# Anchor.net
KiCad netlist of a schematic drawn in Altium Designer
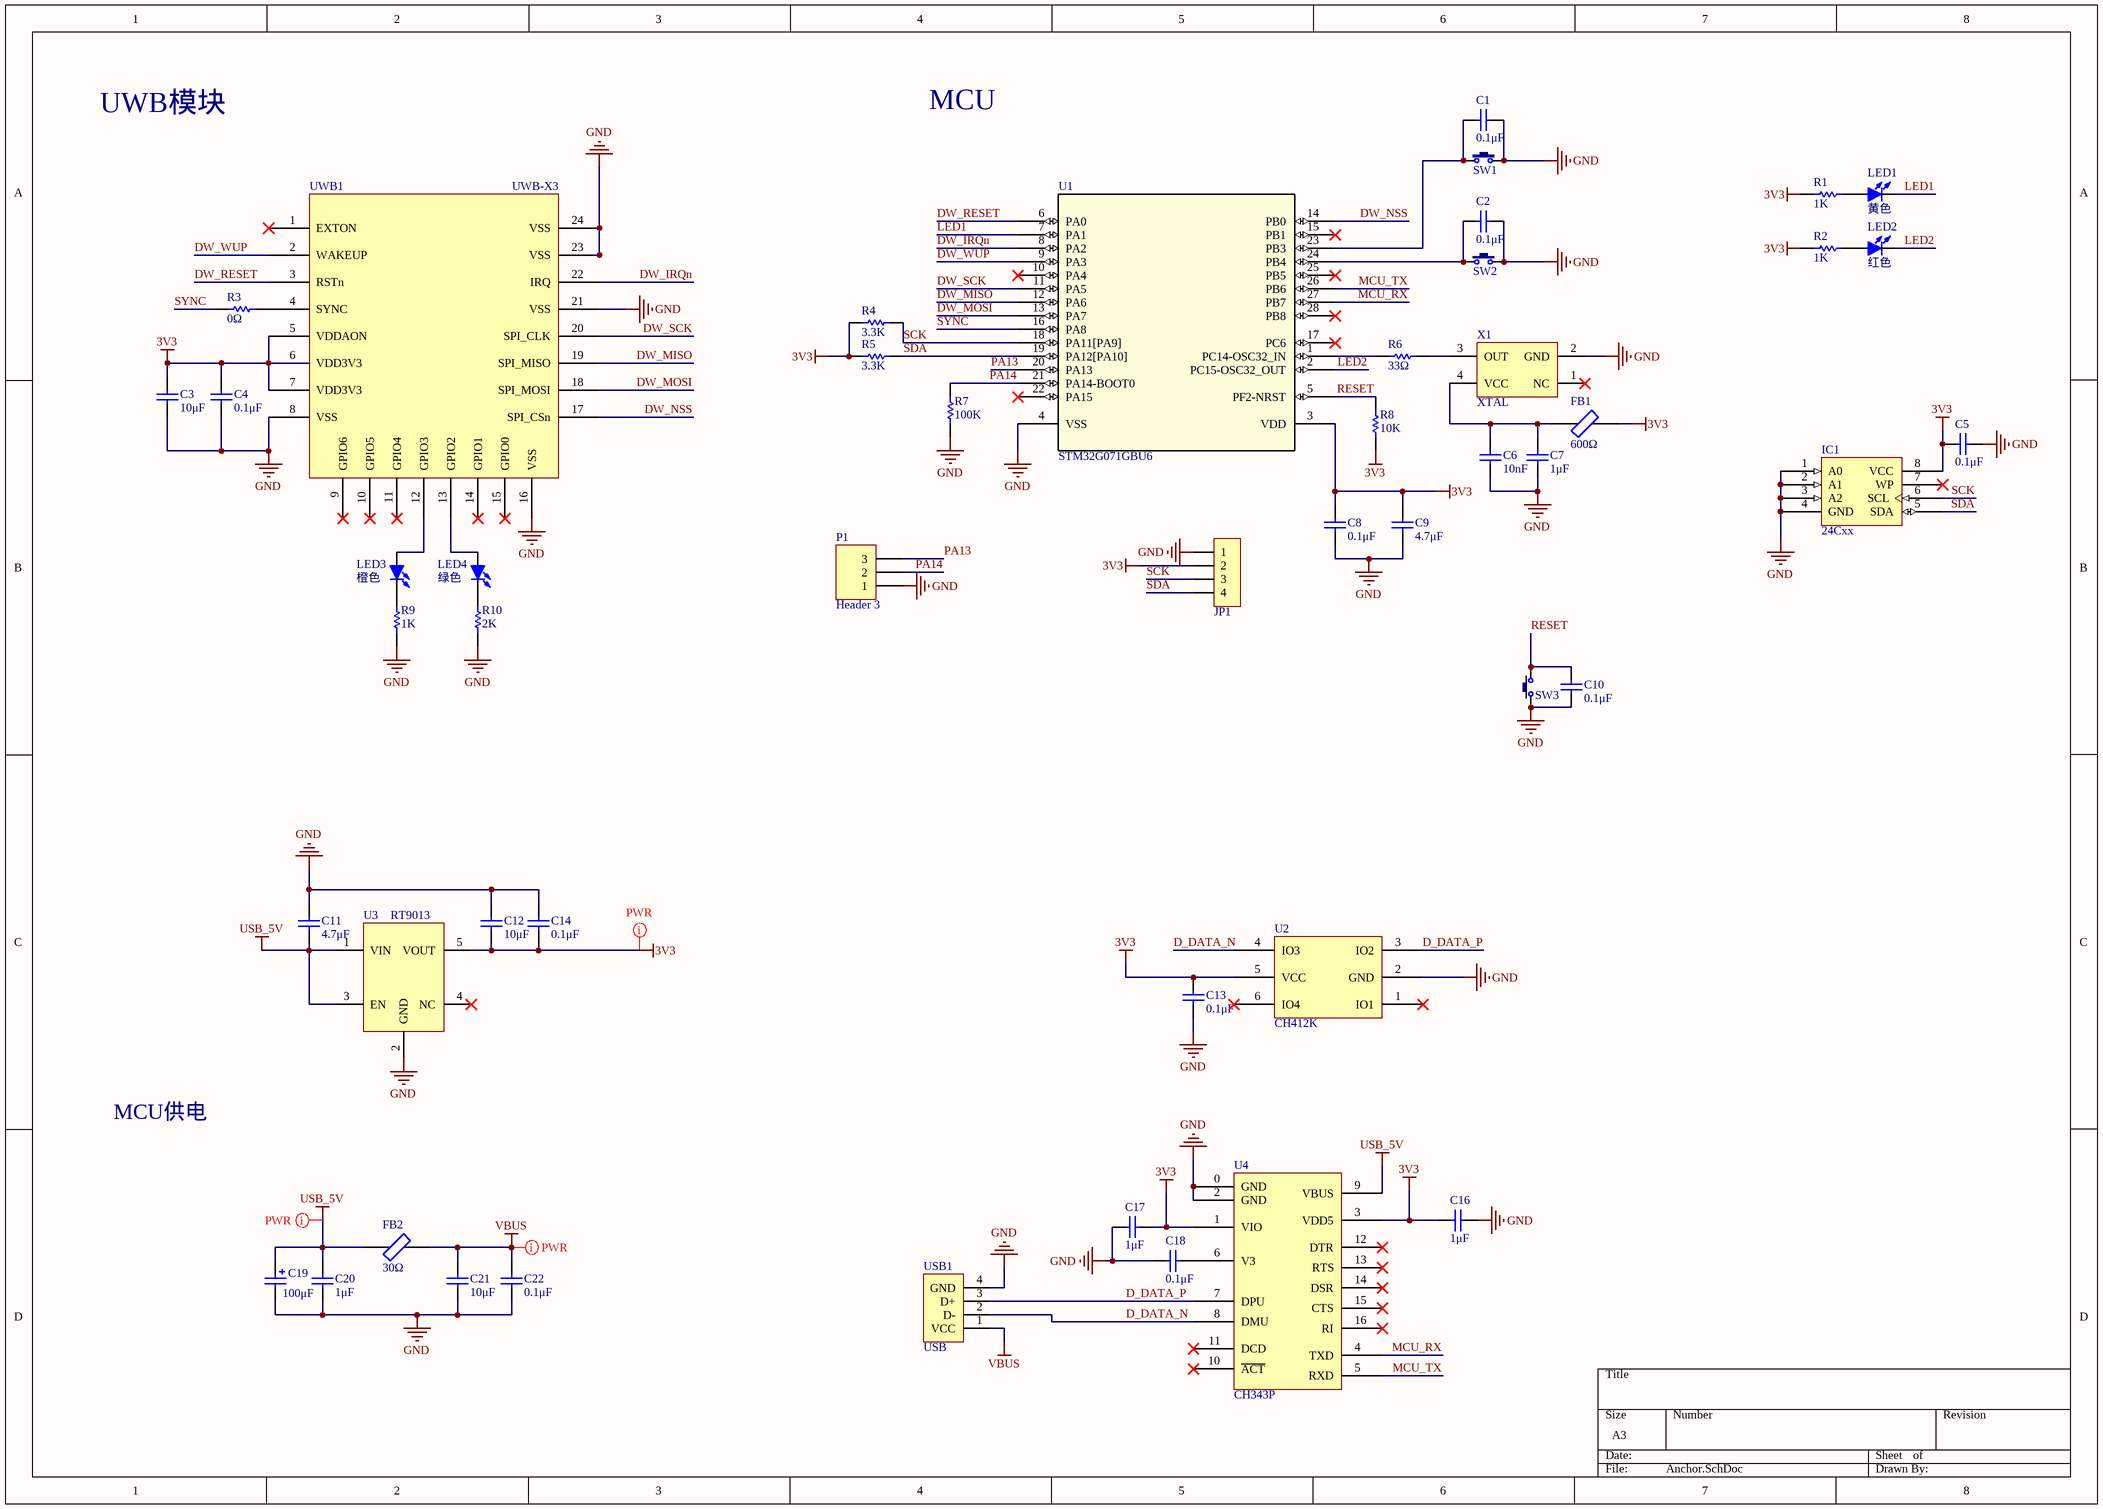
[diagram p0: Anchor.SchDoc]

(export (version "E")
  (design (tool "Eeschema 10.0.6"))
  (components
    (comp (ref "C1")
      (value "0.1μF")
      (footprint "C 0603_L")
      (description "Capacitor")
      (fields (field (name "Comment") "Cap") (field (name "PUBLISHER") "Altium Limited"))
      (libsource (lib "Nixie") (part "Cap"))
    )
    (comp (ref "C2")
      (value "0.1μF")
      (footprint "C 0603_L")
      (description "Capacitor")
      (fields (field (name "Comment") "Cap") (field (name "PUBLISHER") "Altium Limited"))
      (libsource (lib "Nixie") (part "Cap"))
    )
    (comp (ref "C3")
      (value "10μF")
      (footprint "C 0603_L")
      (description "Capacitor")
      (fields (field (name "Comment") "Cap") (field (name "PUBLISHER") "Altium Limited"))
      (libsource (lib "Nixie") (part "Cap"))
    )
    (comp (ref "C4")
      (value "0.1μF")
      (footprint "C 0603_L")
      (description "Capacitor")
      (fields (field (name "Comment") "Cap") (field (name "PUBLISHER") "Altium Limited"))
      (libsource (lib "Nixie") (part "Cap"))
    )
    (comp (ref "C5")
      (value "0.1μF")
      (footprint "C 0603_L")
      (description "Capacitor")
      (fields (field (name "Comment") "Cap") (field (name "PUBLISHER") "Altium Limited"))
      (libsource (lib "Nixie") (part "Cap"))
    )
    (comp (ref "C6")
      (value "10nF")
      (footprint "C 0603_L")
      (description "Capacitor")
      (fields (field (name "Comment") "Cap") (field (name "PUBLISHER") "Altium Limited"))
      (libsource (lib "Nixie") (part "Cap"))
    )
    (comp (ref "C7")
      (value "1μF")
      (footprint "C 0603_L")
      (description "Capacitor")
      (fields (field (name "Comment") "Cap") (field (name "PUBLISHER") "Altium Limited"))
      (libsource (lib "Nixie") (part "Cap"))
    )
    (comp (ref "C8")
      (value "0.1μF")
      (footprint "C 0603_L")
      (description "Capacitor")
      (fields (field (name "Comment") "Cap") (field (name "PUBLISHER") "Altium Limited"))
      (libsource (lib "Nixie") (part "Cap"))
    )
    (comp (ref "C9")
      (value "4.7μF")
      (footprint "C 0603_L")
      (description "Capacitor")
      (fields (field (name "Comment") "Cap") (field (name "PUBLISHER") "Altium Limited"))
      (libsource (lib "Nixie") (part "Cap"))
    )
    (comp (ref "C10")
      (value "0.1μF")
      (footprint "C 0603_L")
      (description "Capacitor")
      (fields (field (name "Comment") "Cap") (field (name "PUBLISHER") "Altium Limited"))
      (libsource (lib "Nixie") (part "Cap"))
    )
    (comp (ref "C11")
      (value "4.7μF")
      (footprint "C 0603_L")
      (description "Capacitor")
      (fields (field (name "Comment") "Cap") (field (name "PUBLISHER") "Altium Limited"))
      (libsource (lib "Nixie") (part "Cap"))
    )
    (comp (ref "C12")
      (value "10μF")
      (footprint "C 0603_L")
      (description "Capacitor")
      (fields (field (name "Comment") "Cap") (field (name "PUBLISHER") "Altium Limited"))
      (libsource (lib "Nixie") (part "Cap"))
    )
    (comp (ref "C13")
      (value "0.1μF")
      (footprint "C 0603_L")
      (description "Capacitor")
      (fields (field (name "Comment") "Cap") (field (name "PUBLISHER") "Altium Limited"))
      (libsource (lib "Nixie") (part "Cap"))
    )
    (comp (ref "C14")
      (value "0.1μF")
      (footprint "C 0603_L")
      (description "Capacitor")
      (fields (field (name "Comment") "Cap") (field (name "PUBLISHER") "Altium Limited"))
      (libsource (lib "Nixie") (part "Cap"))
    )
    (comp (ref "C16")
      (value "1μF")
      (footprint "C 0603_L")
      (description "Capacitor")
      (fields (field (name "Comment") "Cap") (field (name "PUBLISHER") "Altium Limited"))
      (libsource (lib "Nixie") (part "Cap"))
    )
    (comp (ref "C17")
      (value "1μF")
      (footprint "C 0603_L")
      (description "Capacitor")
      (fields (field (name "Comment") "Cap") (field (name "PUBLISHER") "Altium Limited"))
      (libsource (lib "Nixie") (part "Cap"))
    )
    (comp (ref "C18")
      (value "0.1μF")
      (footprint "C 0603_L")
      (description "Capacitor")
      (fields (field (name "Comment") "Cap") (field (name "PUBLISHER") "Altium Limited"))
      (libsource (lib "Nixie") (part "Cap"))
    )
    (comp (ref "C19")
      (value "100μF")
      (footprint "CM C(5*5.4)")
      (description "Polarized Capacitor (Radial)")
      (fields (field (name "Comment") "Cap Pol1") (field (name "PUBLISHER") "Altium Limited"))
      (libsource (lib "Nixie") (part "Cap Pol1"))
    )
    (comp (ref "C20")
      (value "1μF")
      (footprint "C 0603_L")
      (description "Capacitor")
      (fields (field (name "Comment") "Cap") (field (name "PUBLISHER") "Altium Limited"))
      (libsource (lib "Nixie") (part "Cap"))
    )
    (comp (ref "C21")
      (value "10μF")
      (footprint "C 0603_L")
      (description "Capacitor")
      (fields (field (name "Comment") "Cap") (field (name "PUBLISHER") "Altium Limited"))
      (libsource (lib "Nixie") (part "Cap"))
    )
    (comp (ref "C22")
      (value "0.1μF")
      (footprint "C 0603_L")
      (description "Capacitor")
      (fields (field (name "Comment") "Cap") (field (name "PUBLISHER") "Altium Limited"))
      (libsource (lib "Nixie") (part "Cap"))
    )
    (comp (ref "FB1")
      (value "600Ω")
      (footprint "C 0603_L")
      (description "铁氧体磁珠")
      (fields (field (name "Comment") "Ferrite bead"))
      (libsource (lib "Nixie") (part "Ferrite bead"))
    )
    (comp (ref "FB2")
      (value "30Ω")
      (footprint "C 0603_L")
      (description "铁氧体磁珠")
      (fields (field (name "Comment") "Ferrite bead"))
      (libsource (lib "Nixie") (part "Ferrite bead"))
    )
    (comp (ref "IC1")
      (value "24Cxx")
      (footprint "SOP8_L")
      (description "外置EEPROM")
      (fields (field (name "版权归属") "封装库来自淘宝 ID：黄晶宝石"))
      (libsource (lib "Nixie") (part "24Cxx"))
    )
    (comp (ref "JP1")
      (value "HDR-1X4")
      (footprint "HDR2.54-LI-4P")
      (description "4P接插件")
      (fields (field (name "版权归属") "封装库来自淘宝 ID：黄晶宝石"))
      (libsource (lib "Nixie") (part "Header 4"))
    )
    (comp (ref "LED1")
      (value "黄色")
      (footprint "LED 0805G")
      (description "贴片LED")
      (fields (field (name "版权归属") "封装库来自淘宝 ID：黄晶宝石"))
      (libsource (lib "Nixie") (part "LED-SMD"))
    )
    (comp (ref "LED2")
      (value "红色")
      (footprint "LED 0805R")
      (description "贴片LED")
      (fields (field (name "版权归属") "封装库来自淘宝 ID：黄晶宝石"))
      (libsource (lib "Nixie") (part "LED-SMD"))
    )
    (comp (ref "LED3")
      (value "橙色")
      (footprint "LED 0805G")
      (description "贴片LED")
      (fields (field (name "版权归属") "封装库来自淘宝 ID：黄晶宝石"))
      (libsource (lib "Nixie") (part "LED-SMD"))
    )
    (comp (ref "LED4")
      (value "绿色")
      (footprint "LED 0805G")
      (description "贴片LED")
      (fields (field (name "版权归属") "封装库来自淘宝 ID：黄晶宝石"))
      (libsource (lib "Nixie") (part "LED-SMD"))
    )
    (comp (ref "P1")
      (value "Header 3")
      (footprint "HDR2.54-LI-3P")
      (description "Header, 3-Pin")
      (fields (field (name "PUBLISHER") "Altium Limited"))
      (libsource (lib "Miscellaneous Connectors") (part "Header 3"))
    )
    (comp (ref "R1")
      (value "1K")
      (footprint "R 0603_L")
      (description "Resistor")
      (fields (field (name "PUBLISHER") "Altium Limited"))
      (libsource (lib "Nixie") (part "Resistor"))
    )
    (comp (ref "R2")
      (value "1K")
      (footprint "R 0603_L")
      (description "Resistor")
      (fields (field (name "PUBLISHER") "Altium Limited"))
      (libsource (lib "Nixie") (part "Resistor"))
    )
    (comp (ref "R3")
      (value "0Ω")
      (footprint "R 0603_L")
      (description "Resistor")
      (fields (field (name "PUBLISHER") "Altium Limited"))
      (libsource (lib "Nixie") (part "Resistor"))
    )
    (comp (ref "R4")
      (value "3.3K")
      (footprint "R 0603_L")
      (description "Resistor")
      (fields (field (name "PUBLISHER") "Altium Limited"))
      (libsource (lib "Nixie") (part "Resistor"))
    )
    (comp (ref "R5")
      (value "3.3K")
      (footprint "R 0603_L")
      (description "Resistor")
      (fields (field (name "PUBLISHER") "Altium Limited"))
      (libsource (lib "Nixie") (part "Resistor"))
    )
    (comp (ref "R6")
      (value "33Ω")
      (footprint "R 0603_L")
      (description "Resistor")
      (fields (field (name "PUBLISHER") "Altium Limited"))
      (libsource (lib "Nixie") (part "Resistor"))
    )
    (comp (ref "R7")
      (value "100K")
      (footprint "R 0603_L")
      (description "Resistor")
      (fields (field (name "PUBLISHER") "Altium Limited"))
      (libsource (lib "Nixie") (part "Resistor"))
    )
    (comp (ref "R8")
      (value "10K")
      (footprint "R 0603_L")
      (description "Resistor")
      (fields (field (name "PUBLISHER") "Altium Limited"))
      (libsource (lib "Nixie") (part "Resistor"))
    )
    (comp (ref "R9")
      (value "1K")
      (footprint "R 0603_L")
      (description "Resistor")
      (fields (field (name "PUBLISHER") "Altium Limited"))
      (libsource (lib "Nixie") (part "Resistor"))
    )
    (comp (ref "R10")
      (value "2K")
      (footprint "R 0603_L")
      (description "Resistor")
      (fields (field (name "PUBLISHER") "Altium Limited"))
      (libsource (lib "Nixie") (part "Resistor"))
    )
    (comp (ref "SW1")
      (value "3x6x5")
      (footprint "TSW SMD-3*6*2.5")
      (description "3x6轻触开关")
      (fields (field (name "版权归属") "封装库来自淘宝 ID：黄晶宝石"))
      (libsource (lib "Nixie") (part "TSW 3x6"))
    )
    (comp (ref "SW2")
      (value "3x6x5")
      (footprint "TSW SMD-3*6*2.5")
      (description "3x6轻触开关")
      (fields (field (name "版权归属") "封装库来自淘宝 ID：黄晶宝石"))
      (libsource (lib "Nixie") (part "TSW 3x6"))
    )
    (comp (ref "SW3")
      (value "3x6x5")
      (footprint "TSW SMD-3*6*2.5")
      (description "3x6轻触开关")
      (fields (field (name "版权归属") "封装库来自淘宝 ID：黄晶宝石"))
      (libsource (lib "") (part "TSW 3x6_1"))
    )
    (comp (ref "U1")
      (value "STM32G071GBU6")
      (footprint "UFQFPN-28")
      (description "No Description Available")
      (libsource (lib "Nixie") (part "STM32G071GBU6"))
    )
    (comp (ref "U2")
      (value "CH412K")
      (footprint "SOT-363")
      (description "四路ESD保护")
      (libsource (lib "Nixie") (part "CH412K"))
    )
    (comp (ref "U3")
      (value "RT9013")
      (footprint "SOT23-5L")
      (description "LDO")
      (libsource (lib "HandHeld_terminal") (part "RT9013"))
    )
    (comp (ref "U4")
      (value "CH343P")
      (footprint "QFN16")
      (description "USB转串口")
      (libsource (lib "Nixie") (part "CH343"))
    )
    (comp (ref "USB1")
      (value "USB")
      (footprint "USB_A/P_B")
      (description "USB-A型公接口")
      (fields (field (name "版权归属") "封装库来自淘宝卖家 ID：黄晶宝石"))
      (libsource (lib "Nixie") (part "USB-A/P"))
    )
    (comp (ref "UWB1")
      (value "UWB-X3")
      (footprint "UWB-X3-MAX-IPEX")
      (libsource (lib "Nixie") (part "UWB-X3(DWM3000)"))
    )
    (comp (ref "X1")
      (value "XTAL")
      (footprint "OSC 3225-4P")
      (description "4脚有源晶振")
      (libsource (lib "Nixie") (part "XTAL"))
    )
  )
  (nets
    (net (code "1") (name "/DW_IRQn") (class "Default")
      (node (ref "U1") (pin "8") (pinfunction "PA2_8") (pintype "bidirectional"))
      (node (ref "UWB1") (pin "22") (pinfunction "IRQ_22") (pintype "passive"))
    )
    (net (code "2") (name "/DW_MISO") (class "Default")
      (node (ref "U1") (pin "12") (pinfunction "PA6_12") (pintype "bidirectional"))
      (node (ref "UWB1") (pin "19") (pinfunction "SPI_MISO_19") (pintype "passive"))
    )
    (net (code "3") (name "/DW_MOSI") (class "Default")
      (node (ref "U1") (pin "13") (pinfunction "PA7_13") (pintype "bidirectional"))
      (node (ref "UWB1") (pin "18") (pinfunction "SPI_MOSI_18") (pintype "passive"))
    )
    (net (code "4") (name "/DW_NSS") (class "Default")
      (node (ref "U1") (pin "14") (pinfunction "PB0_14") (pintype "bidirectional"))
      (node (ref "UWB1") (pin "17") (pinfunction "SPI_CSn_17") (pintype "passive"))
    )
    (net (code "5") (name "/DW_RESET") (class "Default")
      (node (ref "U1") (pin "6") (pinfunction "PA0_6") (pintype "bidirectional"))
      (node (ref "UWB1") (pin "3") (pinfunction "RSTn_3") (pintype "passive"))
    )
    (net (code "6") (name "/DW_SCK") (class "Default")
      (node (ref "U1") (pin "11") (pinfunction "PA5_11") (pintype "bidirectional"))
      (node (ref "UWB1") (pin "20") (pinfunction "SPI_CLK_20") (pintype "passive"))
    )
    (net (code "7") (name "/DW_WUP") (class "Default")
      (node (ref "U1") (pin "9") (pinfunction "PA3_9") (pintype "bidirectional"))
      (node (ref "UWB1") (pin "2") (pinfunction "WAKEUP_2") (pintype "passive"))
    )
    (net (code "8") (name "/D_DATA_N") (class "Default")
      (node (ref "U2") (pin "4") (pinfunction "IO3_4") (pintype "passive"))
      (node (ref "U4") (pin "8") (pinfunction "DMU_8") (pintype "passive"))
      (node (ref "USB1") (pin "2") (pinfunction "D-_2") (pintype "passive"))
    )
    (net (code "9") (name "/D_DATA_P") (class "Default")
      (node (ref "U2") (pin "3") (pinfunction "IO2_3") (pintype "passive"))
      (node (ref "U4") (pin "7") (pinfunction "DPU_7") (pintype "passive"))
      (node (ref "USB1") (pin "3") (pinfunction "D+_3") (pintype "passive"))
    )
    (net (code "10") (name "/LED1") (class "Default")
      (node (ref "LED1") (pin "2") (pinfunction "K_2") (pintype "passive"))
      (node (ref "U1") (pin "7") (pinfunction "PA1_7") (pintype "bidirectional"))
    )
    (net (code "11") (name "/LED2") (class "Default")
      (node (ref "LED2") (pin "2") (pinfunction "K_2") (pintype "passive"))
      (node (ref "U1") (pin "2") (pinfunction "PC15-OSC32_OUT_2") (pintype "bidirectional"))
    )
    (net (code "12") (name "/MCU_RX") (class "Default")
      (node (ref "U1") (pin "27") (pinfunction "PB7_27") (pintype "bidirectional"))
      (node (ref "U4") (pin "4") (pinfunction "TXD_4") (pintype "passive"))
    )
    (net (code "13") (name "/MCU_TX") (class "Default")
      (node (ref "U1") (pin "26") (pinfunction "PB6_26") (pintype "bidirectional"))
      (node (ref "U4") (pin "5") (pinfunction "RXD_5") (pintype "passive"))
    )
    (net (code "14") (name "/PA13") (class "Default")
      (node (ref "P1") (pin "3") (pinfunction "3_3") (pintype "passive"))
      (node (ref "U1") (pin "20") (pinfunction "PA13_20") (pintype "bidirectional"))
    )
    (net (code "15") (name "/PA14") (class "Default")
      (node (ref "P1") (pin "2") (pinfunction "2_2") (pintype "passive"))
      (node (ref "R7") (pin "1") (pinfunction "1_1") (pintype "passive"))
      (node (ref "U1") (pin "21") (pinfunction "PA14-BOOT0_21") (pintype "bidirectional"))
    )
    (net (code "16") (name "/RESET") (class "Default")
      (node (ref "C10") (pin "2") (pinfunction "2_2") (pintype "passive"))
      (node (ref "R8") (pin "1") (pinfunction "1_1") (pintype "passive"))
      (node (ref "SW3") (pin "2") (pinfunction "2_2") (pintype "passive"))
      (node (ref "U1") (pin "5") (pinfunction "PF2-NRST_5") (pintype "bidirectional"))
    )
    (net (code "17") (name "/SCK") (class "Default")
      (node (ref "IC1") (pin "6") (pinfunction "SCL_6") (pintype "input"))
      (node (ref "JP1") (pin "3") (pinfunction "3_3") (pintype "passive"))
      (node (ref "R4") (pin "2") (pinfunction "2_2") (pintype "passive"))
      (node (ref "U1") (pin "18") (pinfunction "PA11[PA9]_18") (pintype "bidirectional"))
    )
    (net (code "18") (name "/SDA") (class "Default")
      (node (ref "IC1") (pin "5") (pinfunction "SDA_5") (pintype "bidirectional"))
      (node (ref "JP1") (pin "4") (pinfunction "4_4") (pintype "passive"))
      (node (ref "R5") (pin "2") (pinfunction "2_2") (pintype "passive"))
      (node (ref "U1") (pin "19") (pinfunction "PA12[PA10]_19") (pintype "bidirectional"))
    )
    (net (code "19") (name "/SYNC") (class "Default")
      (node (ref "R3") (pin "1") (pinfunction "1_1") (pintype "passive"))
      (node (ref "U1") (pin "16") (pinfunction "PA8_16") (pintype "bidirectional"))
    )
    (net (code "20") (name "3V3") (class "Default")
      (node (ref "C12") (pin "1") (pinfunction "1_1") (pintype "passive"))
      (node (ref "C13") (pin "2") (pinfunction "2_2") (pintype "passive"))
      (node (ref "C14") (pin "1") (pinfunction "1_1") (pintype "passive"))
      (node (ref "C16") (pin "1") (pinfunction "1_1") (pintype "passive"))
      (node (ref "C17") (pin "2") (pinfunction "2_2") (pintype "passive"))
      (node (ref "C3") (pin "2") (pinfunction "2_2") (pintype "passive"))
      (node (ref "C4") (pin "1") (pinfunction "1_1") (pintype "passive"))
      (node (ref "C5") (pin "2") (pinfunction "2_2") (pintype "passive"))
      (node (ref "C8") (pin "2") (pinfunction "2_2") (pintype "passive"))
      (node (ref "C9") (pin "1") (pinfunction "1_1") (pintype "passive"))
      (node (ref "FB1") (pin "2") (pinfunction "2_2") (pintype "passive"))
      (node (ref "IC1") (pin "8") (pinfunction "VCC_8") (pintype "power_in"))
      (node (ref "JP1") (pin "2") (pinfunction "2_2") (pintype "passive"))
      (node (ref "R1") (pin "2") (pinfunction "2_2") (pintype "passive"))
      (node (ref "R2") (pin "2") (pinfunction "2_2") (pintype "passive"))
      (node (ref "R4") (pin "1") (pinfunction "1_1") (pintype "passive"))
      (node (ref "R5") (pin "1") (pinfunction "1_1") (pintype "passive"))
      (node (ref "R8") (pin "2") (pinfunction "2_2") (pintype "passive"))
      (node (ref "U1") (pin "3") (pinfunction "VDD_3") (pintype "power_in"))
      (node (ref "U2") (pin "5") (pinfunction "VCC_5") (pintype "passive"))
      (node (ref "U3") (pin "5") (pinfunction "VOUT_5") (pintype "passive"))
      (node (ref "U4") (pin "1") (pinfunction "VIO_1") (pintype "passive"))
      (node (ref "U4") (pin "3") (pinfunction "VDD5_3") (pintype "passive"))
      (node (ref "UWB1") (pin "5") (pinfunction "VDDAON_5") (pintype "passive"))
      (node (ref "UWB1") (pin "6") (pinfunction "VDD3V3_6") (pintype "passive"))
      (node (ref "UWB1") (pin "7") (pinfunction "VDD3V3_7") (pintype "passive"))
    )
    (net (code "21") (name "GND") (class "Default")
      (node (ref "C1") (pin "1") (pinfunction "1_1") (pintype "passive"))
      (node (ref "C10") (pin "1") (pinfunction "1_1") (pintype "passive"))
      (node (ref "C11") (pin "2") (pinfunction "2_2") (pintype "passive"))
      (node (ref "C12") (pin "2") (pinfunction "2_2") (pintype "passive"))
      (node (ref "C13") (pin "1") (pinfunction "1_1") (pintype "passive"))
      (node (ref "C14") (pin "2") (pinfunction "2_2") (pintype "passive"))
      (node (ref "C16") (pin "2") (pinfunction "2_2") (pintype "passive"))
      (node (ref "C17") (pin "1") (pinfunction "1_1") (pintype "passive"))
      (node (ref "C18") (pin "1") (pinfunction "1_1") (pintype "passive"))
      (node (ref "C19") (pin "2") (pinfunction "2_2") (pintype "passive"))
      (node (ref "C2") (pin "1") (pinfunction "1_1") (pintype "passive"))
      (node (ref "C20") (pin "1") (pinfunction "1_1") (pintype "passive"))
      (node (ref "C21") (pin "1") (pinfunction "1_1") (pintype "passive"))
      (node (ref "C22") (pin "1") (pinfunction "1_1") (pintype "passive"))
      (node (ref "C3") (pin "1") (pinfunction "1_1") (pintype "passive"))
      (node (ref "C4") (pin "2") (pinfunction "2_2") (pintype "passive"))
      (node (ref "C5") (pin "1") (pinfunction "1_1") (pintype "passive"))
      (node (ref "C6") (pin "1") (pinfunction "1_1") (pintype "passive"))
      (node (ref "C7") (pin "1") (pinfunction "1_1") (pintype "passive"))
      (node (ref "C8") (pin "1") (pinfunction "1_1") (pintype "passive"))
      (node (ref "C9") (pin "2") (pinfunction "2_2") (pintype "passive"))
      (node (ref "IC1") (pin "1") (pinfunction "A0_1") (pintype "input"))
      (node (ref "IC1") (pin "2") (pinfunction "A1_2") (pintype "input"))
      (node (ref "IC1") (pin "3") (pinfunction "A2_3") (pintype "input"))
      (node (ref "IC1") (pin "4") (pinfunction "GND_4") (pintype "passive"))
      (node (ref "JP1") (pin "1") (pinfunction "1_1") (pintype "passive"))
      (node (ref "P1") (pin "1") (pinfunction "1_1") (pintype "passive"))
      (node (ref "R10") (pin "2") (pinfunction "2_2") (pintype "passive"))
      (node (ref "R7") (pin "2") (pinfunction "2_2") (pintype "passive"))
      (node (ref "R9") (pin "2") (pinfunction "2_2") (pintype "passive"))
      (node (ref "SW1") (pin "2") (pinfunction "2_2") (pintype "passive"))
      (node (ref "SW2") (pin "2") (pinfunction "2_2") (pintype "passive"))
      (node (ref "SW3") (pin "1") (pinfunction "1_1") (pintype "passive"))
      (node (ref "U1") (pin "4") (pinfunction "VSS_4") (pintype "power_in"))
      (node (ref "U2") (pin "2") (pinfunction "GND_2") (pintype "passive"))
      (node (ref "U3") (pin "2") (pinfunction "GND_2") (pintype "passive"))
      (node (ref "U4") (pin "0") (pinfunction "GND_0") (pintype "passive"))
      (node (ref "U4") (pin "2") (pinfunction "GND_2") (pintype "passive"))
      (node (ref "USB1") (pin "4") (pinfunction "GND_4") (pintype "passive"))
      (node (ref "UWB1") (pin "16") (pinfunction "VSS_16") (pintype "passive"))
      (node (ref "UWB1") (pin "21") (pinfunction "VSS_21") (pintype "passive"))
      (node (ref "UWB1") (pin "23") (pinfunction "VSS_23") (pintype "passive"))
      (node (ref "UWB1") (pin "24") (pinfunction "VSS_24") (pintype "passive"))
      (node (ref "UWB1") (pin "8") (pinfunction "VSS_8") (pintype "passive"))
      (node (ref "X1") (pin "2") (pinfunction "GND_2") (pintype "passive"))
    )
    (net (code "22") (name "Net-(LED1-A)") (class "Default")
      (node (ref "LED1") (pin "1") (pinfunction "A_1") (pintype "passive"))
      (node (ref "R1") (pin "1") (pinfunction "1_1") (pintype "passive"))
    )
    (net (code "23") (name "Net-(LED2-A)") (class "Default")
      (node (ref "LED2") (pin "1") (pinfunction "A_1") (pintype "passive"))
      (node (ref "R2") (pin "1") (pinfunction "1_1") (pintype "passive"))
    )
    (net (code "24") (name "Net-(LED3-A)") (class "Default")
      (node (ref "LED3") (pin "1") (pinfunction "A_1") (pintype "passive"))
      (node (ref "UWB1") (pin "12") (pinfunction "GPIO3_12") (pintype "passive"))
    )
    (net (code "25") (name "Net-(LED3-K)") (class "Default")
      (node (ref "LED3") (pin "2") (pinfunction "K_2") (pintype "passive"))
      (node (ref "R9") (pin "1") (pinfunction "1_1") (pintype "passive"))
    )
    (net (code "26") (name "Net-(LED4-A)") (class "Default")
      (node (ref "LED4") (pin "1") (pinfunction "A_1") (pintype "passive"))
      (node (ref "UWB1") (pin "13") (pinfunction "GPIO2_13") (pintype "passive"))
    )
    (net (code "27") (name "Net-(LED4-K)") (class "Default")
      (node (ref "LED4") (pin "2") (pinfunction "K_2") (pintype "passive"))
      (node (ref "R10") (pin "1") (pinfunction "1_1") (pintype "passive"))
    )
    (net (code "28") (name "Net-(U1-PB3)") (class "Default")
      (node (ref "C1") (pin "2") (pinfunction "2_2") (pintype "passive"))
      (node (ref "SW1") (pin "1") (pinfunction "1_1") (pintype "passive"))
      (node (ref "U1") (pin "23") (pinfunction "PB3_23") (pintype "bidirectional"))
    )
    (net (code "29") (name "Net-(U1-PB4)") (class "Default")
      (node (ref "C2") (pin "2") (pinfunction "2_2") (pintype "passive"))
      (node (ref "SW2") (pin "1") (pinfunction "1_1") (pintype "passive"))
      (node (ref "U1") (pin "24") (pinfunction "PB4_24") (pintype "bidirectional"))
    )
    (net (code "30") (name "Net-(U1-PC14-OSC32_IN)") (class "Default")
      (node (ref "R6") (pin "1") (pinfunction "1_1") (pintype "passive"))
      (node (ref "U1") (pin "1") (pinfunction "PC14-OSC32_IN_1") (pintype "bidirectional"))
    )
    (net (code "31") (name "Net-(U4-V3)") (class "Default")
      (node (ref "C18") (pin "2") (pinfunction "2_2") (pintype "passive"))
      (node (ref "U4") (pin "6") (pinfunction "V3_6") (pintype "passive"))
    )
    (net (code "32") (name "Net-(UWB1-SYNC)") (class "Default")
      (node (ref "R3") (pin "2") (pinfunction "2_2") (pintype "passive"))
      (node (ref "UWB1") (pin "4") (pinfunction "SYNC_4") (pintype "passive"))
    )
    (net (code "33") (name "Net-(X1-OUT)") (class "Default")
      (node (ref "R6") (pin "2") (pinfunction "2_2") (pintype "passive"))
      (node (ref "X1") (pin "3") (pinfunction "OUT_3") (pintype "passive"))
    )
    (net (code "34") (name "Net-(X1-VCC)") (class "Default")
      (node (ref "C6") (pin "2") (pinfunction "2_2") (pintype "passive"))
      (node (ref "C7") (pin "2") (pinfunction "2_2") (pintype "passive"))
      (node (ref "FB1") (pin "1") (pinfunction "1_1") (pintype "passive"))
      (node (ref "X1") (pin "4") (pinfunction "VCC_4") (pintype "passive"))
    )
    (net (code "35") (name "USB_5V") (class "Default")
      (node (ref "C11") (pin "1") (pinfunction "1_1") (pintype "passive"))
      (node (ref "C19") (pin "1") (pinfunction "1_1") (pintype "passive"))
      (node (ref "C20") (pin "2") (pinfunction "2_2") (pintype "passive"))
      (node (ref "FB2") (pin "1") (pinfunction "1_1") (pintype "passive"))
      (node (ref "U3") (pin "1") (pinfunction "VIN_1") (pintype "passive"))
      (node (ref "U3") (pin "3") (pinfunction "EN_3") (pintype "passive"))
      (node (ref "U4") (pin "9") (pinfunction "VBUS_9") (pintype "passive"))
    )
    (net (code "36") (name "VBUS") (class "Default")
      (node (ref "C21") (pin "2") (pinfunction "2_2") (pintype "passive"))
      (node (ref "C22") (pin "2") (pinfunction "2_2") (pintype "passive"))
      (node (ref "FB2") (pin "2") (pinfunction "2_2") (pintype "passive"))
      (node (ref "USB1") (pin "1") (pinfunction "VCC_1") (pintype "passive"))
    )
    (net (code "37") (name "unconnected-(IC1-WP-Pad7)") (class "Default")
      (node (ref "IC1") (pin "7") (pinfunction "WP_7") (pintype "passive+no_connect"))
    )
    (net (code "38") (name "unconnected-(U1-PA4-Pad10)") (class "Default")
      (node (ref "U1") (pin "10") (pinfunction "PA4_10") (pintype "bidirectional+no_connect"))
    )
    (net (code "39") (name "unconnected-(U1-PA15-Pad22)") (class "Default")
      (node (ref "U1") (pin "22") (pinfunction "PA15_22") (pintype "bidirectional+no_connect"))
    )
    (net (code "40") (name "unconnected-(U1-PB1-Pad15)") (class "Default")
      (node (ref "U1") (pin "15") (pinfunction "PB1_15") (pintype "bidirectional+no_connect"))
    )
    (net (code "41") (name "unconnected-(U1-PB5-Pad25)") (class "Default")
      (node (ref "U1") (pin "25") (pinfunction "PB5_25") (pintype "bidirectional+no_connect"))
    )
    (net (code "42") (name "unconnected-(U1-PB8-Pad28)") (class "Default")
      (node (ref "U1") (pin "28") (pinfunction "PB8_28") (pintype "bidirectional+no_connect"))
    )
    (net (code "43") (name "unconnected-(U1-PC6-Pad17)") (class "Default")
      (node (ref "U1") (pin "17") (pinfunction "PC6_17") (pintype "bidirectional+no_connect"))
    )
    (net (code "44") (name "unconnected-(U2-IO1-Pad1)") (class "Default")
      (node (ref "U2") (pin "1") (pinfunction "IO1_1") (pintype "passive+no_connect"))
    )
    (net (code "45") (name "unconnected-(U2-IO4-Pad6)") (class "Default")
      (node (ref "U2") (pin "6") (pinfunction "IO4_6") (pintype "passive+no_connect"))
    )
    (net (code "46") (name "unconnected-(U3-NC-Pad4)") (class "Default")
      (node (ref "U3") (pin "4") (pinfunction "NC_4") (pintype "passive+no_connect"))
    )
    (net (code "47") (name "unconnected-(U4-CTS-Pad15)") (class "Default")
      (node (ref "U4") (pin "15") (pinfunction "CTS_15") (pintype "passive+no_connect"))
    )
    (net (code "48") (name "unconnected-(U4-DCD-Pad11)") (class "Default")
      (node (ref "U4") (pin "11") (pinfunction "DCD_11") (pintype "passive+no_connect"))
    )
    (net (code "49") (name "unconnected-(U4-DSR-Pad14)") (class "Default")
      (node (ref "U4") (pin "14") (pinfunction "DSR_14") (pintype "passive+no_connect"))
    )
    (net (code "50") (name "unconnected-(U4-DTR-Pad12)") (class "Default")
      (node (ref "U4") (pin "12") (pinfunction "DTR_12") (pintype "passive+no_connect"))
    )
    (net (code "51") (name "unconnected-(U4-RI-Pad16)") (class "Default")
      (node (ref "U4") (pin "16") (pinfunction "RI_16") (pintype "passive+no_connect"))
    )
    (net (code "52") (name "unconnected-(U4-RTS-Pad13)") (class "Default")
      (node (ref "U4") (pin "13") (pinfunction "RTS_13") (pintype "passive+no_connect"))
    )
    (net (code "53") (name "unconnected-(U4-~{ACT}-Pad10)") (class "Default")
      (node (ref "U4") (pin "10") (pinfunction "~{ACT}_10") (pintype "passive+no_connect"))
    )
    (net (code "54") (name "unconnected-(UWB1-EXTON-Pad1)") (class "Default")
      (node (ref "UWB1") (pin "1") (pinfunction "EXTON_1") (pintype "passive+no_connect"))
    )
    (net (code "55") (name "unconnected-(UWB1-GPIO0-Pad15)") (class "Default")
      (node (ref "UWB1") (pin "15") (pinfunction "GPIO0_15") (pintype "passive+no_connect"))
    )
    (net (code "56") (name "unconnected-(UWB1-GPIO1-Pad14)") (class "Default")
      (node (ref "UWB1") (pin "14") (pinfunction "GPIO1_14") (pintype "passive+no_connect"))
    )
    (net (code "57") (name "unconnected-(UWB1-GPIO4-Pad11)") (class "Default")
      (node (ref "UWB1") (pin "11") (pinfunction "GPIO4_11") (pintype "passive+no_connect"))
    )
    (net (code "58") (name "unconnected-(UWB1-GPIO5-Pad10)") (class "Default")
      (node (ref "UWB1") (pin "10") (pinfunction "GPIO5_10") (pintype "passive+no_connect"))
    )
    (net (code "59") (name "unconnected-(UWB1-GPIO6-Pad9)") (class "Default")
      (node (ref "UWB1") (pin "9") (pinfunction "GPIO6_9") (pintype "passive+no_connect"))
    )
    (net (code "60") (name "unconnected-(X1-NC-Pad1)") (class "Default")
      (node (ref "X1") (pin "1") (pinfunction "NC_1") (pintype "passive+no_connect"))
    )
  )
)
